# BLUENRG-M2SA.net
KiCad netlist of a schematic drawn in Altium Designer
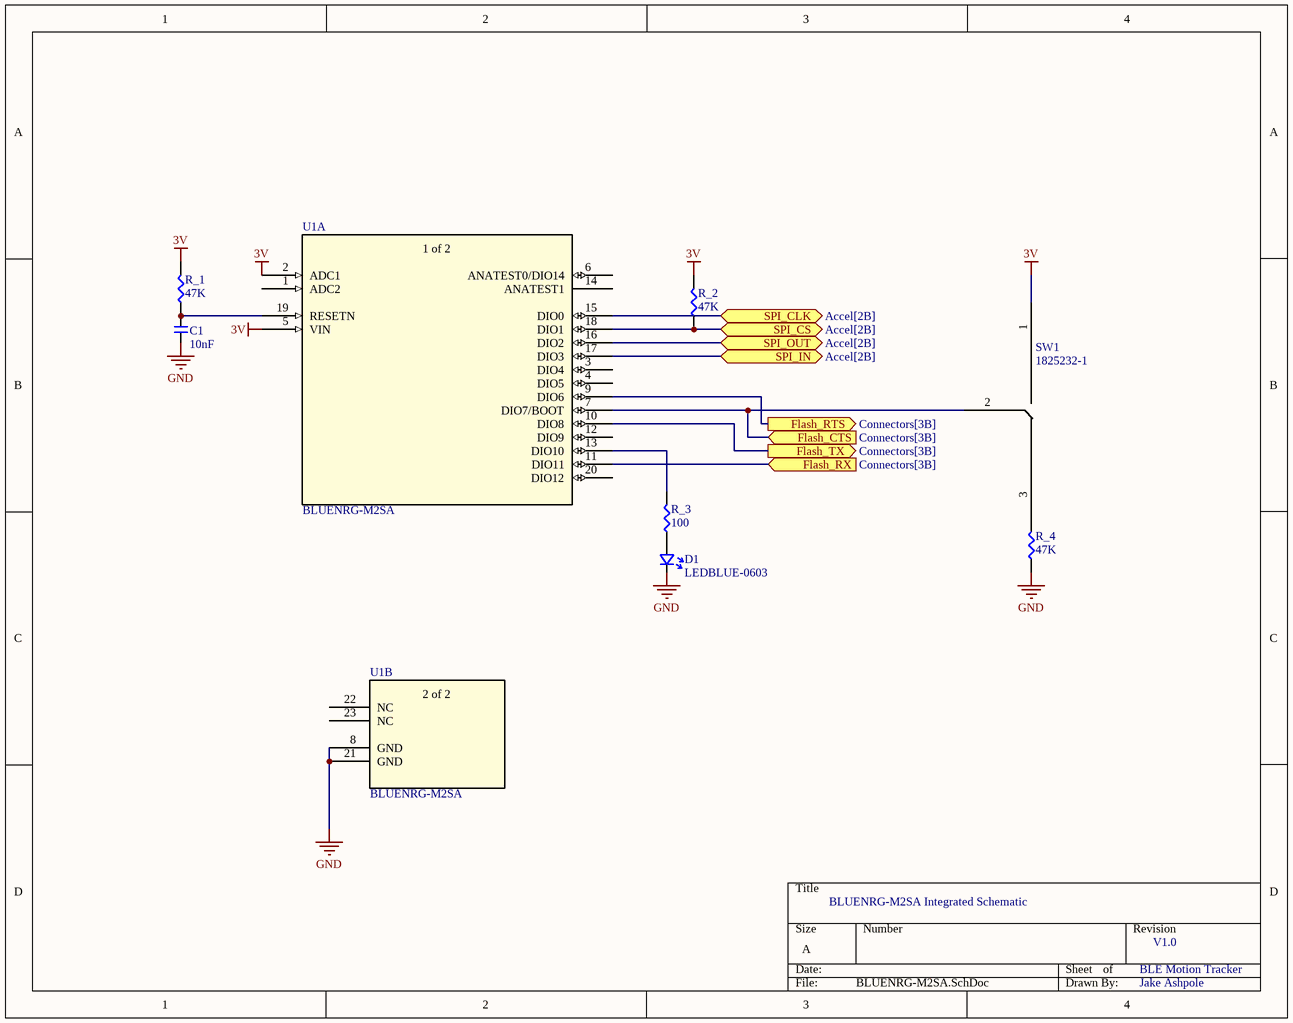
[diagram p0: BLUENRG-M2SA.SchDoc]

(export (version "E")
  (design (tool "Eeschema 10.0.6"))
  (components
    (comp (ref "C1")
      (value "10nF")
      (footprint "CAP-0603")
      (fields (field (name "SOURCE") "ife19_Elec_Library.SchLib"))
      (libsource (lib "Illini Formula Electric") (part "CAP-0603"))
    )
    (comp (ref "D1")
      (value "LEDBLUE-0603")
      (footprint "LEDBLUE-0603")
      (fields (field (name "SOURCE") "ife19_Elec_Library.SchLib"))
      (libsource (lib "Illini Formula Electric") (part "LEDBLUE-0603"))
    )
    (comp (ref "R_1")
      (value "47K")
      (footprint "RES-0603")
      (fields (field (name "SOURCE") "ife19_Elec_Library.SchLib"))
      (libsource (lib "Illini Formula Electric") (part "Symbol"))
    )
    (comp (ref "R_2")
      (value "47K")
      (footprint "RES-0603")
      (fields (field (name "SOURCE") "ife19_Elec_Library.SchLib"))
      (libsource (lib "Illini Formula Electric") (part "Symbol"))
    )
    (comp (ref "R_3")
      (value "100")
      (footprint "RES-0603")
      (fields (field (name "SOURCE") "ife19_Elec_Library.SchLib"))
      (libsource (lib "Illini Formula Electric") (part "Symbol"))
    )
    (comp (ref "R_4")
      (value "47K")
      (footprint "RES-0603")
      (fields (field (name "SOURCE") "ife19_Elec_Library.SchLib"))
      (libsource (lib "Illini Formula Electric") (part "Symbol"))
    )
    (comp (ref "SW1")
      (value "1825232-1")
      (footprint "1825232-1_TEC")
      (description "https://www.mouser.com/ProductDetail/655-1825232-1")
      (libsource (lib "1825232-1") (part "1825232-1"))
    )
    (comp (ref "U1")
      (value "BLUENRG-M2SA")
      (footprint "BLUENRG-2M_STM")
      (libsource (lib "BLUENRG-M2SA") (part "BLUENRG-M2SA"))
    )
  )
  (nets
    (net (code "1") (name "/Flash_CTS") (class "Default")
      (node (ref "SW1") (pin "2") (pinfunction "2_2") (pintype "passive"))
      (node (ref "U1") (pin "7") (pinfunction "DIO7/BOOT_7") (pintype "bidirectional"))
    )
    (net (code "2") (name "/Flash_RTS") (class "Default")
      (node (ref "U1") (pin "9") (pinfunction "DIO6_9") (pintype "bidirectional"))
    )
    (net (code "3") (name "/Flash_RX") (class "Default")
      (node (ref "U1") (pin "11") (pinfunction "DIO11_11") (pintype "bidirectional"))
    )
    (net (code "4") (name "/Flash_TX") (class "Default")
      (node (ref "U1") (pin "10") (pinfunction "DIO8_10") (pintype "bidirectional"))
    )
    (net (code "5") (name "/SPI_CLK") (class "Default")
      (node (ref "U1") (pin "15") (pinfunction "DIO0_15") (pintype "bidirectional"))
    )
    (net (code "6") (name "/SPI_CS") (class "Default")
      (node (ref "R_2") (pin "1") (pinfunction "1_1") (pintype "passive"))
      (node (ref "U1") (pin "18") (pinfunction "DIO1_18") (pintype "bidirectional"))
    )
    (net (code "7") (name "/SPI_IN") (class "Default")
      (node (ref "U1") (pin "17") (pinfunction "DIO3_17") (pintype "bidirectional"))
    )
    (net (code "8") (name "/SPI_OUT") (class "Default")
      (node (ref "U1") (pin "16") (pinfunction "DIO2_16") (pintype "bidirectional"))
    )
    (net (code "9") (name "3V") (class "Default")
      (node (ref "R_1") (pin "2") (pinfunction "2_2") (pintype "passive"))
      (node (ref "R_2") (pin "2") (pinfunction "2_2") (pintype "passive"))
      (node (ref "SW1") (pin "1") (pinfunction "1_1") (pintype "passive"))
      (node (ref "U1") (pin "2") (pinfunction "ADC1_2") (pintype "input"))
      (node (ref "U1") (pin "5") (pinfunction "VIN_5") (pintype "input"))
    )
    (net (code "10") (name "GND") (class "Default")
      (node (ref "C1") (pin "1") (pinfunction "1_1") (pintype "passive"))
      (node (ref "D1") (pin "K") (pinfunction "K_K") (pintype "passive"))
      (node (ref "R_4") (pin "1") (pinfunction "1_1") (pintype "passive"))
      (node (ref "U1") (pin "21") (pinfunction "GND_21") (pintype "power_in"))
      (node (ref "U1") (pin "8") (pinfunction "GND_8") (pintype "power_in"))
    )
    (net (code "11") (name "Net-(D1-PadA)") (class "Default")
      (node (ref "D1") (pin "A") (pinfunction "A_A") (pintype "passive"))
      (node (ref "R_3") (pin "1") (pinfunction "1_1") (pintype "passive"))
    )
    (net (code "12") (name "Net-(R_4-Pad2)") (class "Default")
      (node (ref "R_4") (pin "2") (pinfunction "2_2") (pintype "passive"))
      (node (ref "SW1") (pin "3") (pinfunction "3_3") (pintype "passive"))
    )
    (net (code "13") (name "Net-(U1A-DIO10)") (class "Default")
      (node (ref "R_3") (pin "2") (pinfunction "2_2") (pintype "passive"))
      (node (ref "U1") (pin "13") (pinfunction "DIO10_13") (pintype "bidirectional"))
    )
    (net (code "14") (name "Net-(U1A-RESETN)") (class "Default")
      (node (ref "C1") (pin "2") (pinfunction "2_2") (pintype "passive"))
      (node (ref "R_1") (pin "1") (pinfunction "1_1") (pintype "passive"))
      (node (ref "U1") (pin "19") (pinfunction "RESETN_19") (pintype "input"))
    )
    (net (code "15") (name "unconnected-(U1A-ADC2-Pad1)") (class "Default")
      (node (ref "U1") (pin "1") (pinfunction "ADC2_1") (pintype "input"))
    )
    (net (code "16") (name "unconnected-(U1A-ANATEST0{slash}DIO14-Pad6)") (class "Default")
      (node (ref "U1") (pin "6") (pinfunction "ANATEST0/DIO14_6") (pintype "bidirectional"))
    )
    (net (code "17") (name "unconnected-(U1A-ANATEST1-Pad14)") (class "Default")
      (node (ref "U1") (pin "14") (pinfunction "ANATEST1_14") (pintype "passive"))
    )
    (net (code "18") (name "unconnected-(U1A-DIO4-Pad3)") (class "Default")
      (node (ref "U1") (pin "3") (pinfunction "DIO4_3") (pintype "bidirectional"))
    )
    (net (code "19") (name "unconnected-(U1A-DIO5-Pad4)") (class "Default")
      (node (ref "U1") (pin "4") (pinfunction "DIO5_4") (pintype "bidirectional"))
    )
    (net (code "20") (name "unconnected-(U1A-DIO9-Pad12)") (class "Default")
      (node (ref "U1") (pin "12") (pinfunction "DIO9_12") (pintype "bidirectional"))
    )
    (net (code "21") (name "unconnected-(U1A-DIO12-Pad20)") (class "Default")
      (node (ref "U1") (pin "20") (pinfunction "DIO12_20") (pintype "bidirectional"))
    )
    (net (code "22") (name "unconnected-(U1B-NC-Pad22)") (class "Default")
      (node (ref "U1") (pin "22") (pinfunction "NC_22") (pintype "passive"))
    )
    (net (code "23") (name "unconnected-(U1B-NC-Pad23)") (class "Default")
      (node (ref "U1") (pin "23") (pinfunction "NC_23") (pintype "passive"))
    )
  )
)
